# tb6612-breakout.net
KiCad netlist of a schematic drawn in EAGLE
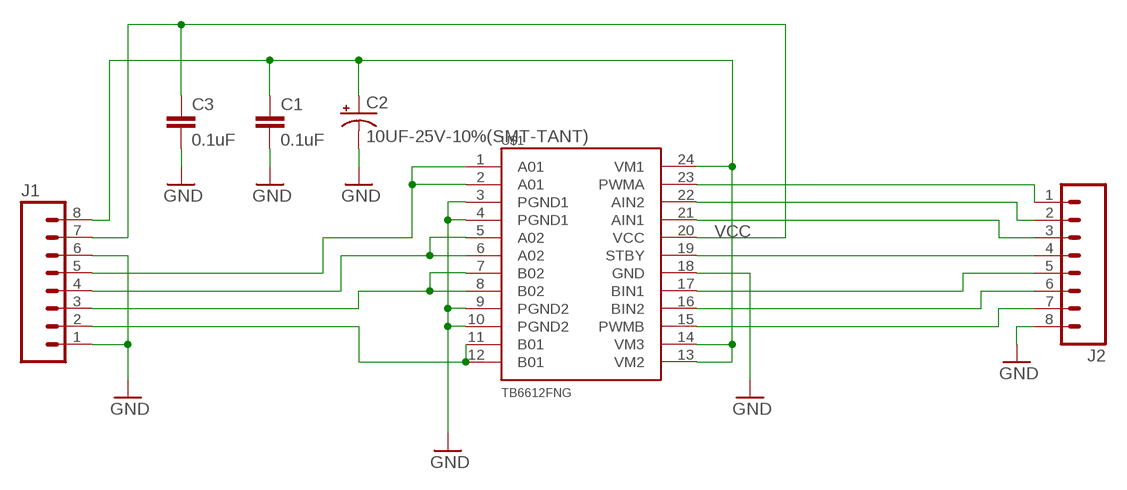
[diagram p0: schematic, sheet 1]

(export (version "E")
  (design (tool "Eeschema 10.0.6"))
  (components
    (comp (ref "C1")
      (value "0.1uF")
      (footprint "eagle-import:0603-CAP")
      (libsource (lib "eagle-import") (part "0.1UF-25V(+80/-20%)(0603)"))
    )
    (comp (ref "C2")
      (value "10UF-25V-10%(SMT-TANT)")
      (footprint "eagle-import:EIA6032-NOM")
      (libsource (lib "eagle-import") (part "10UF-25V-10%(SMT-TANT)"))
    )
    (comp (ref "C3")
      (value "0.1uF")
      (footprint "eagle-import:0603-CAP")
      (libsource (lib "eagle-import") (part "0.1UF-25V(+80/-20%)(0603)"))
    )
    (comp (ref "J1")
      (value "M08SILK_FEMALE_PTH")
      (footprint "eagle-import:1X08")
      (libsource (lib "eagle-import") (part "M08SILK_FEMALE_PTH"))
    )
    (comp (ref "J2")
      (value "M08SILK_FEMALE_PTH")
      (footprint "eagle-import:1X08")
      (libsource (lib "eagle-import") (part "M08SILK_FEMALE_PTH"))
    )
    (comp (ref "U$1")
      (value "TB6612FNG")
      (footprint "eagle-import:SSOP24")
      (libsource (lib "eagle-import") (part "TB6612FNG"))
    )
  )
  (nets
    (net (code "1") (name "/VCC") (class "Default")
      (node (ref "C3") (pin "1") (pinfunction "1_1") (pintype "passive"))
      (node (ref "J1") (pin "7") (pinfunction "7_7") (pintype "passive"))
      (node (ref "U$1") (pin "20") (pinfunction "VCC_20") (pintype "bidirectional"))
    )
    (net (code "2") (name "GND") (class "Default")
      (node (ref "C1") (pin "2") (pinfunction "2_2") (pintype "passive"))
      (node (ref "C2") (pin "C") (pinfunction "-_C") (pintype "passive"))
      (node (ref "C3") (pin "2") (pinfunction "2_2") (pintype "passive"))
      (node (ref "J1") (pin "1") (pinfunction "1_1") (pintype "passive"))
      (node (ref "J1") (pin "6") (pinfunction "6_6") (pintype "passive"))
      (node (ref "J2") (pin "8") (pinfunction "8_8") (pintype "passive"))
      (node (ref "U$1") (pin "10") (pinfunction "PGND2_10") (pintype "bidirectional"))
      (node (ref "U$1") (pin "18") (pinfunction "GND_18") (pintype "bidirectional"))
      (node (ref "U$1") (pin "3") (pinfunction "PGND1_3") (pintype "bidirectional"))
      (node (ref "U$1") (pin "4") (pinfunction "PGND1_4") (pintype "bidirectional"))
      (node (ref "U$1") (pin "9") (pinfunction "PGND2_9") (pintype "bidirectional"))
    )
    (net (code "3") (name "Net-(C2-+)") (class "Default")
      (node (ref "C1") (pin "1") (pinfunction "1_1") (pintype "passive"))
      (node (ref "C2") (pin "A") (pinfunction "+_A") (pintype "passive"))
      (node (ref "J1") (pin "8") (pinfunction "8_8") (pintype "passive"))
      (node (ref "U$1") (pin "13") (pinfunction "VM2_13") (pintype "bidirectional"))
      (node (ref "U$1") (pin "14") (pinfunction "VM3_14") (pintype "bidirectional"))
      (node (ref "U$1") (pin "24") (pinfunction "VM1_24") (pintype "bidirectional"))
    )
    (net (code "4") (name "Net-(J1-Pad2)") (class "Default")
      (node (ref "J1") (pin "2") (pinfunction "2_2") (pintype "passive"))
      (node (ref "U$1") (pin "11") (pinfunction "B01_11") (pintype "bidirectional"))
      (node (ref "U$1") (pin "12") (pinfunction "B01_12") (pintype "bidirectional"))
    )
    (net (code "5") (name "Net-(J1-Pad3)") (class "Default")
      (node (ref "J1") (pin "3") (pinfunction "3_3") (pintype "passive"))
      (node (ref "U$1") (pin "7") (pinfunction "B02_7") (pintype "bidirectional"))
      (node (ref "U$1") (pin "8") (pinfunction "B02_8") (pintype "bidirectional"))
    )
    (net (code "6") (name "Net-(J1-Pad4)") (class "Default")
      (node (ref "J1") (pin "4") (pinfunction "4_4") (pintype "passive"))
      (node (ref "U$1") (pin "5") (pinfunction "A02_5") (pintype "bidirectional"))
      (node (ref "U$1") (pin "6") (pinfunction "A02_6") (pintype "bidirectional"))
    )
    (net (code "7") (name "Net-(J1-Pad5)") (class "Default")
      (node (ref "J1") (pin "5") (pinfunction "5_5") (pintype "passive"))
      (node (ref "U$1") (pin "1") (pinfunction "A01_1") (pintype "bidirectional"))
      (node (ref "U$1") (pin "2") (pinfunction "A01_2") (pintype "bidirectional"))
    )
    (net (code "8") (name "Net-(U$1-AIN1)") (class "Default")
      (node (ref "J2") (pin "3") (pinfunction "3_3") (pintype "passive"))
      (node (ref "U$1") (pin "21") (pinfunction "AIN1_21") (pintype "bidirectional"))
    )
    (net (code "9") (name "Net-(U$1-AIN2)") (class "Default")
      (node (ref "J2") (pin "2") (pinfunction "2_2") (pintype "passive"))
      (node (ref "U$1") (pin "22") (pinfunction "AIN2_22") (pintype "bidirectional"))
    )
    (net (code "10") (name "Net-(U$1-BIN1)") (class "Default")
      (node (ref "J2") (pin "5") (pinfunction "5_5") (pintype "passive"))
      (node (ref "U$1") (pin "17") (pinfunction "BIN1_17") (pintype "bidirectional"))
    )
    (net (code "11") (name "Net-(U$1-BIN2)") (class "Default")
      (node (ref "J2") (pin "6") (pinfunction "6_6") (pintype "passive"))
      (node (ref "U$1") (pin "16") (pinfunction "BIN2_16") (pintype "bidirectional"))
    )
    (net (code "12") (name "Net-(U$1-PWMA)") (class "Default")
      (node (ref "J2") (pin "1") (pinfunction "1_1") (pintype "passive"))
      (node (ref "U$1") (pin "23") (pinfunction "PWMA_23") (pintype "bidirectional"))
    )
    (net (code "13") (name "Net-(U$1-PWMB)") (class "Default")
      (node (ref "J2") (pin "7") (pinfunction "7_7") (pintype "passive"))
      (node (ref "U$1") (pin "15") (pinfunction "PWMB_15") (pintype "bidirectional"))
    )
    (net (code "14") (name "Net-(U$1-STBY)") (class "Default")
      (node (ref "J2") (pin "4") (pinfunction "4_4") (pintype "passive"))
      (node (ref "U$1") (pin "19") (pinfunction "STBY_19") (pintype "bidirectional"))
    )
  )
)
